# dcdc_converter.net
KiCad netlist of a schematic drawn in Altium Designer
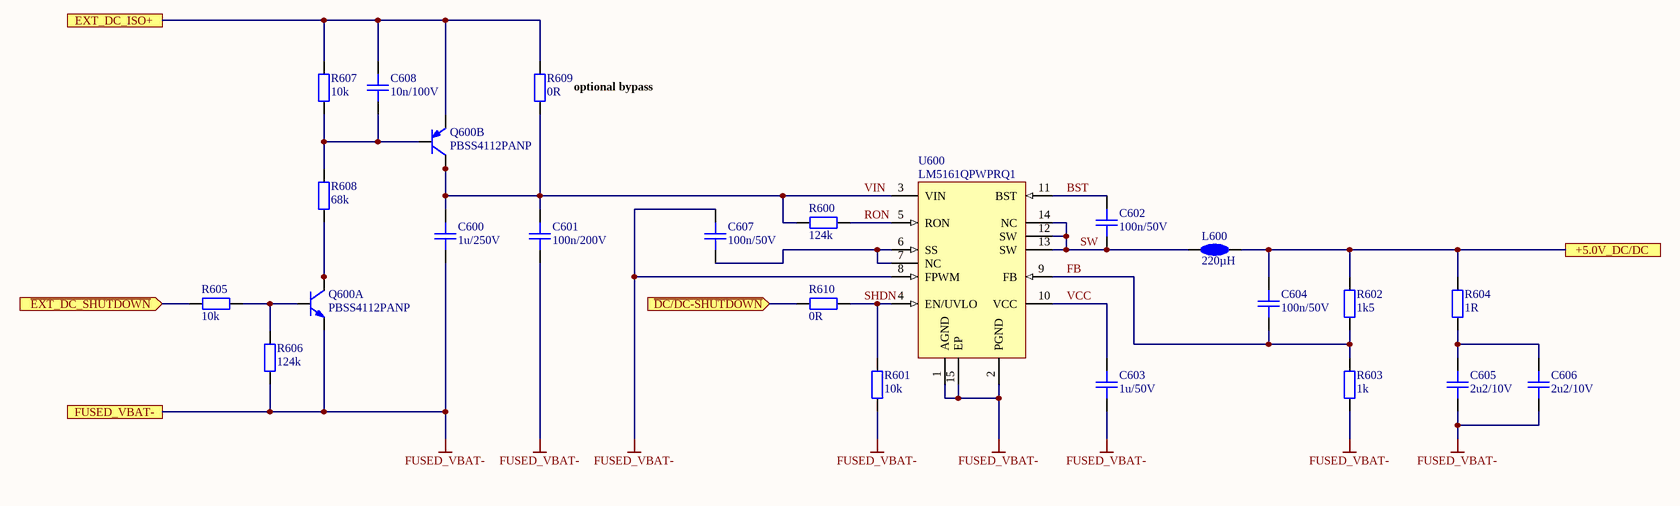
[diagram p0: dcdc_converter.SchDoc]

(export (version "E")
  (design (tool "Eeschema 10.0.6"))
  (components
    (comp (ref "C600")
      (value "1u/250V")
      (footprint "CAPC4532X16N")
      (description "MLCC")
      (fields (field (name "PART NUMBER") "gen_C_ceramic_1u_250V_X7R_1812"))
      (libsource (lib "OE750") (part "C"))
    )
    (comp (ref "C601")
      (value "100n/200V")
      (footprint "CAPC3216X18N")
      (description "MLCC")
      (fields (field (name "PART NUMBER") "gen_C_ceramic_100n_200V_X7R_1206"))
      (libsource (lib "OE750") (part "C"))
    )
    (comp (ref "C602")
      (value "100n/50V")
      (footprint "CAPC1608X08N")
      (description "MLCC")
      (fields (field (name "PART NUMBER") "gen_C_ceramic_100n_50V_X7R_0603"))
      (libsource (lib "OE750") (part "C"))
    )
    (comp (ref "C603")
      (value "1u/50V")
      (footprint "CAPC2012X14N")
      (description "MLCC")
      (fields (field (name "PART NUMBER") "gen_C_ceramic_1u_50V_X7R_0805") (field (name "TOLERANCE") "± 10%"))
      (libsource (lib "OE750") (part "C"))
    )
    (comp (ref "C604")
      (value "100n/50V")
      (footprint "CAPC1608X08N")
      (description "MLCC")
      (fields (field (name "PART NUMBER") "gen_C_ceramic_100n_50V_X7R_0603"))
      (libsource (lib "OE750") (part "C"))
    )
    (comp (ref "C605")
      (value "2u2/10V")
      (footprint "CAPC2012X14N")
      (description "MLCC")
      (fields (field (name "PART NUMBER") "gen_C_ceramic_2u2_10V_X7R_0805"))
      (libsource (lib "OE750") (part "C"))
    )
    (comp (ref "C606")
      (value "2u2/10V")
      (footprint "CAPC2012X14N")
      (description "MLCC")
      (fields (field (name "PART NUMBER") "gen_C_ceramic_2u2_10V_X7R_0805"))
      (libsource (lib "OE750") (part "C"))
    )
    (comp (ref "C607")
      (value "100n/50V")
      (footprint "CAPC1608X08N")
      (description "MLCC")
      (fields (field (name "PART NUMBER") "gen_C_ceramic_100n_50V_X7R_0603"))
      (libsource (lib "OE750") (part "C"))
    )
    (comp (ref "C608")
      (value "10n/100V")
      (footprint "CAPC1608X08N")
      (description "MLCC")
      (fields (field (name "PART NUMBER") "gen_C_ceramic_10n_100V_X7R_0603"))
      (libsource (lib "OE750") (part "C"))
    )
    (comp (ref "L600")
      (value "220µH")
      (footprint "TYS6045221M-10")
      (description "Power Inductor")
      (fields
        (field (name "PART NUMBER") "TYS6045221M-10")
        (field (name "MANUFACTURER") "Laird-Signal Integrity Products")
      )
      (libsource (lib "OE750") (part "L"))
    )
    (comp (ref "Q600")
      (value "PBSS4112PANP")
      (footprint "PBSS4112PANP")
      (description "Dual NPN/PNP Transistor")
      (fields (field (name "MANUFACTURER") "Nexperia"))
      (libsource (lib "OE750") (part "PBSS4112PANP"))
    )
    (comp (ref "R600")
      (value "124k")
      (footprint "RESC1608X05N")
      (description "SMD Resistor 124k 0603")
      (fields (field (name "PART NUMBER") "gen_R_124k_0603") (field (name "TOLERANCE") "1%"))
      (libsource (lib "OE750") (part "R"))
    )
    (comp (ref "R601")
      (value "10k")
      (footprint "RESC1608X05N")
      (description "SMD Resistor 10k 0603")
      (fields (field (name "PART NUMBER") "gen_R_10k_0603") (field (name "TOLERANCE") "1%"))
      (libsource (lib "OE750") (part "R"))
    )
    (comp (ref "R602")
      (value "1k5")
      (footprint "RESC1608X05N")
      (description "SMD Resistor 1k5 0603")
      (fields (field (name "PART NUMBER") "gen_R_1k5_0603") (field (name "TOLERANCE") "1%"))
      (libsource (lib "OE750") (part "R"))
    )
    (comp (ref "R603")
      (value "1k")
      (footprint "RESC1608X05N")
      (description "SMD Resistor 1k 0603")
      (fields (field (name "PART NUMBER") "gen_R_1k_0603") (field (name "TOLERANCE") "1%"))
      (libsource (lib "OE750") (part "R"))
    )
    (comp (ref "R604")
      (value "1R")
      (footprint "RESC2012X05N")
      (description "SMD Resistor 1R 0805")
      (fields (field (name "PART NUMBER") "gen_R_1R_0805") (field (name "TOLERANCE") "1%"))
      (libsource (lib "OE750") (part "R"))
    )
    (comp (ref "R605")
      (value "10k")
      (footprint "RESC1608X05N")
      (description "SMD Resistor 10k 0603")
      (fields (field (name "PART NUMBER") "gen_R_10k_0603") (field (name "TOLERANCE") "1%"))
      (libsource (lib "OE750") (part "R"))
    )
    (comp (ref "R606")
      (value "124k")
      (footprint "RESC1608X05N")
      (description "SMD Resistor 124k 0603")
      (fields (field (name "PART NUMBER") "gen_R_124k_0603") (field (name "TOLERANCE") "1%"))
      (libsource (lib "OE750") (part "R"))
    )
    (comp (ref "R607")
      (value "10k")
      (footprint "RESC1608X05N")
      (description "SMD Resistor 10k 0603")
      (fields (field (name "PART NUMBER") "gen_R_10k_0603") (field (name "TOLERANCE") "1%"))
      (libsource (lib "OE750") (part "R"))
    )
    (comp (ref "R608")
      (value "68k")
      (footprint "RESC1608X05N")
      (description "SMD Resistor 68k 0603")
      (fields (field (name "PART NUMBER") "gen_R_68k_0603") (field (name "TOLERANCE") "1%"))
      (libsource (lib "OE750") (part "R"))
    )
    (comp (ref "R609")
      (value "0R")
      (footprint "RESC1608X05N")
      (description "SMD Resistor 0R 0603")
      (fields (field (name "PART NUMBER") "gen_R_0R_0603") (field (name "POWER") "0.1W"))
      (libsource (lib "OE750") (part "R"))
    )
    (comp (ref "R610")
      (value "0R")
      (footprint "RESC1608X05N")
      (description "SMD Resistor 0R 0603")
      (fields (field (name "PART NUMBER") "gen_R_0R_0603") (field (name "POWER") "0.1W"))
      (libsource (lib "OE750") (part "R"))
    )
    (comp (ref "U600")
      (value "LM5161QPWPRQ1")
      (footprint "PWP0014A")
      (description "Automotive DC/DC buck converter")
      (fields (field (name "MANUFACTURER") "Texas Instruments"))
      (libsource (lib "OE750") (part "LM5161QPWPRQ1"))
    )
  )
  (nets
    (net (code "1") (name "/+5.0V_DC{slash}DC") (class "Default")
      (node (ref "C604") (pin "2") (pinfunction "2_2") (pintype "passive"))
      (node (ref "L600") (pin "2") (pinfunction "2_2") (pintype "passive"))
      (node (ref "R602") (pin "1") (pinfunction "1_1") (pintype "passive"))
      (node (ref "R604") (pin "1") (pinfunction "1_1") (pintype "passive"))
    )
    (net (code "2") (name "/BST") (class "Default")
      (node (ref "C602") (pin "2") (pinfunction "2_2") (pintype "passive"))
      (node (ref "U600") (pin "11") (pinfunction "BST_11") (pintype "input"))
    )
    (net (code "3") (name "/DC{slash}DC-SHUTDOWN") (class "Default")
      (node (ref "R610") (pin "2") (pinfunction "2_2") (pintype "passive"))
    )
    (net (code "4") (name "/EXT_DC_ISO+") (class "Default")
      (node (ref "C608") (pin "1") (pinfunction "1_1") (pintype "passive"))
      (node (ref "Q600") (pin "4") (pinfunction "E_4") (pintype "passive"))
      (node (ref "R607") (pin "2") (pinfunction "2_2") (pintype "passive"))
      (node (ref "R609") (pin "2") (pinfunction "2_2") (pintype "passive"))
    )
    (net (code "5") (name "/EXT_DC_SHUTDOWN") (class "Default")
      (node (ref "R605") (pin "1") (pinfunction "1_1") (pintype "passive"))
    )
    (net (code "6") (name "/FB") (class "Default")
      (node (ref "C604") (pin "1") (pinfunction "1_1") (pintype "passive"))
      (node (ref "R602") (pin "2") (pinfunction "2_2") (pintype "passive"))
      (node (ref "R603") (pin "1") (pinfunction "1_1") (pintype "passive"))
      (node (ref "U600") (pin "9") (pinfunction "FB_9") (pintype "input"))
    )
    (net (code "7") (name "/RON") (class "Default")
      (node (ref "R600") (pin "1") (pinfunction "1_1") (pintype "passive"))
      (node (ref "U600") (pin "5") (pinfunction "RON_5") (pintype "input"))
    )
    (net (code "8") (name "/SHDN") (class "Default")
      (node (ref "R601") (pin "1") (pinfunction "1_1") (pintype "passive"))
      (node (ref "R610") (pin "1") (pinfunction "1_1") (pintype "passive"))
      (node (ref "U600") (pin "4") (pinfunction "EN/UVLO_4") (pintype "input"))
    )
    (net (code "9") (name "/SW") (class "Default")
      (node (ref "C602") (pin "1") (pinfunction "1_1") (pintype "passive"))
      (node (ref "L600") (pin "1") (pinfunction "1_1") (pintype "passive"))
      (node (ref "U600") (pin "12") (pinfunction "SW_12") (pintype "power_in"))
      (node (ref "U600") (pin "13") (pinfunction "SW_13") (pintype "power_in"))
      (node (ref "U600") (pin "14") (pinfunction "NC_14") (pintype "passive"))
    )
    (net (code "10") (name "/VCC") (class "Default")
      (node (ref "C603") (pin "2") (pinfunction "2_2") (pintype "passive"))
      (node (ref "U600") (pin "10") (pinfunction "VCC_10") (pintype "power_in"))
    )
    (net (code "11") (name "/VIN") (class "Default")
      (node (ref "C600") (pin "2") (pinfunction "2_2") (pintype "passive"))
      (node (ref "C601") (pin "2") (pinfunction "2_2") (pintype "passive"))
      (node (ref "Q600") (pin "3") (pinfunction "C_3") (pintype "passive"))
      (node (ref "Q600") (pin "8") (pinfunction "C_8") (pintype "passive"))
      (node (ref "R600") (pin "2") (pinfunction "2_2") (pintype "passive"))
      (node (ref "R609") (pin "1") (pinfunction "1_1") (pintype "passive"))
      (node (ref "U600") (pin "3") (pinfunction "VIN_3") (pintype "power_in"))
    )
    (net (code "12") (name "FUSED_VBAT-") (class "Default")
      (node (ref "C600") (pin "1") (pinfunction "1_1") (pintype "passive"))
      (node (ref "C601") (pin "1") (pinfunction "1_1") (pintype "passive"))
      (node (ref "C603") (pin "1") (pinfunction "1_1") (pintype "passive"))
      (node (ref "C605") (pin "1") (pinfunction "1_1") (pintype "passive"))
      (node (ref "C606") (pin "1") (pinfunction "1_1") (pintype "passive"))
      (node (ref "C607") (pin "2") (pinfunction "2_2") (pintype "passive"))
      (node (ref "Q600") (pin "1") (pinfunction "E_1") (pintype "passive"))
      (node (ref "R601") (pin "2") (pinfunction "2_2") (pintype "passive"))
      (node (ref "R603") (pin "2") (pinfunction "2_2") (pintype "passive"))
      (node (ref "R606") (pin "1") (pinfunction "1_1") (pintype "passive"))
      (node (ref "U600") (pin "1") (pinfunction "AGND_1") (pintype "power_in"))
      (node (ref "U600") (pin "15") (pinfunction "EP_15") (pintype "power_in"))
      (node (ref "U600") (pin "2") (pinfunction "PGND_2") (pintype "power_in"))
      (node (ref "U600") (pin "8") (pinfunction "FPWM_8") (pintype "input"))
    )
    (net (code "13") (name "Net-(C605-Pad2)") (class "Default")
      (node (ref "C605") (pin "2") (pinfunction "2_2") (pintype "passive"))
      (node (ref "C606") (pin "2") (pinfunction "2_2") (pintype "passive"))
      (node (ref "R604") (pin "2") (pinfunction "2_2") (pintype "passive"))
    )
    (net (code "14") (name "Net-(Q600A-B)") (class "Default")
      (node (ref "Q600") (pin "2") (pinfunction "B_2") (pintype "passive"))
      (node (ref "R605") (pin "2") (pinfunction "2_2") (pintype "passive"))
      (node (ref "R606") (pin "2") (pinfunction "2_2") (pintype "passive"))
    )
    (net (code "15") (name "Net-(Q600A-C-Pad6)") (class "Default")
      (node (ref "Q600") (pin "6") (pinfunction "C_6") (pintype "passive"))
      (node (ref "Q600") (pin "7") (pinfunction "C_7") (pintype "passive"))
      (node (ref "R608") (pin "1") (pinfunction "1_1") (pintype "passive"))
    )
    (net (code "16") (name "Net-(Q600B-B)") (class "Default")
      (node (ref "C608") (pin "2") (pinfunction "2_2") (pintype "passive"))
      (node (ref "Q600") (pin "5") (pinfunction "B_5") (pintype "passive"))
      (node (ref "R607") (pin "1") (pinfunction "1_1") (pintype "passive"))
      (node (ref "R608") (pin "2") (pinfunction "2_2") (pintype "passive"))
    )
    (net (code "17") (name "Net-(U600-SS)") (class "Default")
      (node (ref "C607") (pin "1") (pinfunction "1_1") (pintype "passive"))
      (node (ref "U600") (pin "6") (pinfunction "SS_6") (pintype "input"))
      (node (ref "U600") (pin "7") (pinfunction "NC_7") (pintype "passive"))
    )
  )
)
